# SOIC40_v1_r2.net
KiCad netlist of a schematic drawn in EAGLE
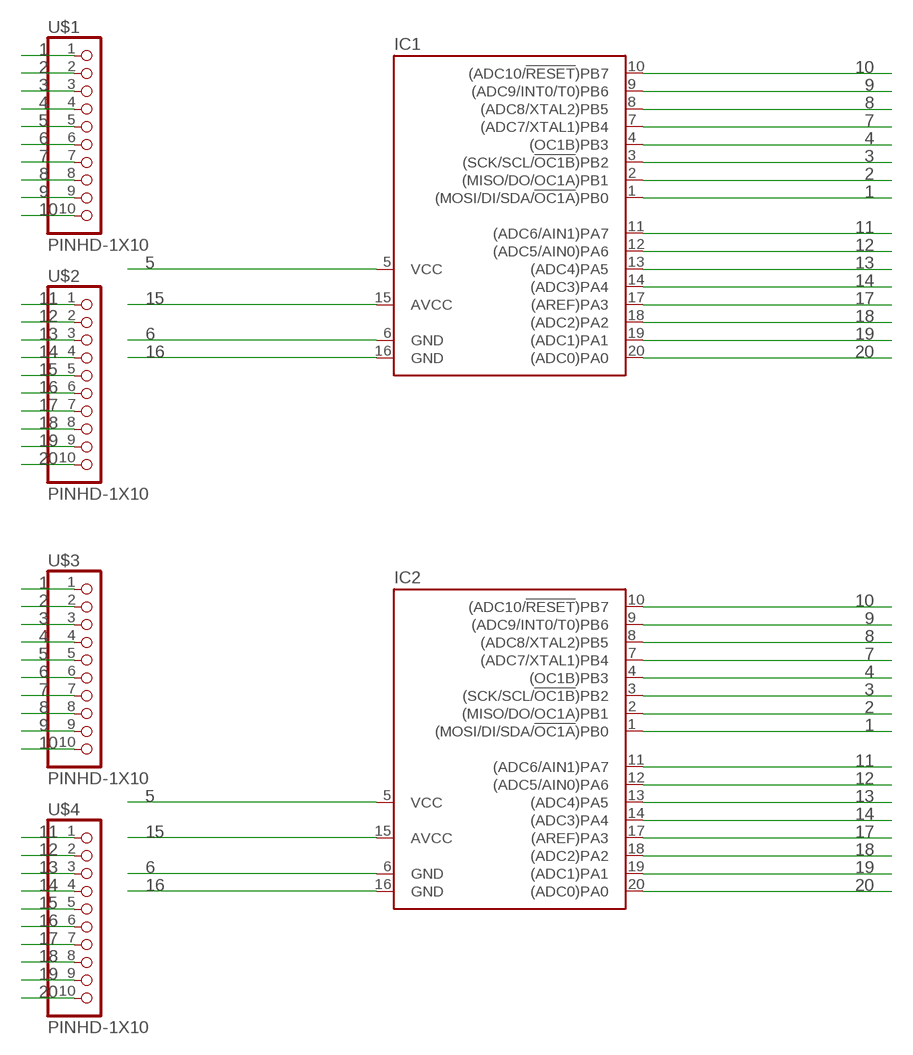
[diagram p0: schematic, sheet 1]

(export (version "E")
  (design (tool "Eeschema 10.0.6"))
  (components
    (comp (ref "IC1")
      (value "TINY26LS")
      (footprint "eagle-import:SO20L")
      (fields (field (name "MPN") "ATTINY26L-8SU"))
      (libsource (lib "eagle-import") (part "TINY26SL"))
    )
    (comp (ref "IC2")
      (value "TINY26LS")
      (footprint "eagle-import:SO20L")
      (fields (field (name "MPN") "ATTINY26L-8SU"))
      (libsource (lib "eagle-import") (part "TINY26SL"))
    )
    (comp (ref "U$1")
      (value "PINHD-1X10")
      (footprint "eagle-import:1X10-BIG")
      (libsource (lib "eagle-import") (part "PINHD-1X10"))
    )
    (comp (ref "U$2")
      (value "PINHD-1X10")
      (footprint "eagle-import:1X10-BIG")
      (libsource (lib "eagle-import") (part "PINHD-1X10"))
    )
    (comp (ref "U$3")
      (value "PINHD-1X10")
      (footprint "eagle-import:1X10-BIG")
      (libsource (lib "eagle-import") (part "PINHD-1X10"))
    )
    (comp (ref "U$4")
      (value "PINHD-1X10")
      (footprint "eagle-import:1X10-BIG")
      (libsource (lib "eagle-import") (part "PINHD-1X10"))
    )
  )
  (nets
    (net (code "1") (name "/1") (class "Default")
      (node (ref "IC1") (pin "1") (pinfunction "(MOSI/DI/SDA/~{OC1A})PB0_1") (pintype "bidirectional"))
      (node (ref "IC2") (pin "1") (pinfunction "(MOSI/DI/SDA/~{OC1A})PB0_1") (pintype "bidirectional"))
      (node (ref "U$1") (pin "1") (pinfunction "1_1") (pintype "passive"))
      (node (ref "U$3") (pin "1") (pinfunction "1_1") (pintype "passive"))
    )
    (net (code "2") (name "/2") (class "Default")
      (node (ref "IC1") (pin "2") (pinfunction "(MISO/DO/OC1A)PB1_2") (pintype "bidirectional"))
      (node (ref "IC2") (pin "2") (pinfunction "(MISO/DO/OC1A)PB1_2") (pintype "bidirectional"))
      (node (ref "U$1") (pin "2") (pinfunction "2_2") (pintype "passive"))
      (node (ref "U$3") (pin "2") (pinfunction "2_2") (pintype "passive"))
    )
    (net (code "3") (name "/3") (class "Default")
      (node (ref "IC1") (pin "3") (pinfunction "(SCK/SCL/~{OC1B})PB2_3") (pintype "bidirectional"))
      (node (ref "IC2") (pin "3") (pinfunction "(SCK/SCL/~{OC1B})PB2_3") (pintype "bidirectional"))
      (node (ref "U$1") (pin "3") (pinfunction "3_3") (pintype "passive"))
      (node (ref "U$3") (pin "3") (pinfunction "3_3") (pintype "passive"))
    )
    (net (code "4") (name "/4") (class "Default")
      (node (ref "IC1") (pin "4") (pinfunction "(OC1B)PB3_4") (pintype "bidirectional"))
      (node (ref "IC2") (pin "4") (pinfunction "(OC1B)PB3_4") (pintype "bidirectional"))
      (node (ref "U$1") (pin "4") (pinfunction "4_4") (pintype "passive"))
      (node (ref "U$3") (pin "4") (pinfunction "4_4") (pintype "passive"))
    )
    (net (code "5") (name "/5") (class "Default")
      (node (ref "IC1") (pin "5") (pinfunction "VCC_5") (pintype "power_in"))
      (node (ref "IC2") (pin "5") (pinfunction "VCC_5") (pintype "power_in"))
      (node (ref "U$1") (pin "5") (pinfunction "5_5") (pintype "passive"))
      (node (ref "U$3") (pin "5") (pinfunction "5_5") (pintype "passive"))
    )
    (net (code "6") (name "/6") (class "Default")
      (node (ref "IC1") (pin "6") (pinfunction "GND_6") (pintype "power_in"))
      (node (ref "IC2") (pin "6") (pinfunction "GND_6") (pintype "power_in"))
      (node (ref "U$1") (pin "6") (pinfunction "6_6") (pintype "passive"))
      (node (ref "U$3") (pin "6") (pinfunction "6_6") (pintype "passive"))
    )
    (net (code "7") (name "/7") (class "Default")
      (node (ref "IC1") (pin "7") (pinfunction "(ADC7/XTAL1)PB4_7") (pintype "bidirectional"))
      (node (ref "IC2") (pin "7") (pinfunction "(ADC7/XTAL1)PB4_7") (pintype "bidirectional"))
      (node (ref "U$1") (pin "7") (pinfunction "7_7") (pintype "passive"))
      (node (ref "U$3") (pin "7") (pinfunction "7_7") (pintype "passive"))
    )
    (net (code "8") (name "/8") (class "Default")
      (node (ref "IC1") (pin "8") (pinfunction "(ADC8/XTAL2)PB5_8") (pintype "bidirectional"))
      (node (ref "IC2") (pin "8") (pinfunction "(ADC8/XTAL2)PB5_8") (pintype "bidirectional"))
      (node (ref "U$1") (pin "8") (pinfunction "8_8") (pintype "passive"))
      (node (ref "U$3") (pin "8") (pinfunction "8_8") (pintype "passive"))
    )
    (net (code "9") (name "/9") (class "Default")
      (node (ref "IC1") (pin "9") (pinfunction "(ADC9/INT0/T0)PB6_9") (pintype "bidirectional"))
      (node (ref "IC2") (pin "9") (pinfunction "(ADC9/INT0/T0)PB6_9") (pintype "bidirectional"))
      (node (ref "U$1") (pin "9") (pinfunction "9_9") (pintype "passive"))
      (node (ref "U$3") (pin "9") (pinfunction "9_9") (pintype "passive"))
    )
    (net (code "10") (name "/10") (class "Default")
      (node (ref "IC1") (pin "10") (pinfunction "(ADC10/~{RESET})PB7_10") (pintype "bidirectional"))
      (node (ref "IC2") (pin "10") (pinfunction "(ADC10/~{RESET})PB7_10") (pintype "bidirectional"))
      (node (ref "U$1") (pin "10") (pinfunction "10_10") (pintype "passive"))
      (node (ref "U$3") (pin "10") (pinfunction "10_10") (pintype "passive"))
    )
    (net (code "11") (name "/11") (class "Default")
      (node (ref "IC1") (pin "11") (pinfunction "(ADC6/AIN1)PA7_11") (pintype "bidirectional"))
      (node (ref "IC2") (pin "11") (pinfunction "(ADC6/AIN1)PA7_11") (pintype "bidirectional"))
      (node (ref "U$2") (pin "1") (pinfunction "1_1") (pintype "passive"))
      (node (ref "U$4") (pin "1") (pinfunction "1_1") (pintype "passive"))
    )
    (net (code "12") (name "/12") (class "Default")
      (node (ref "IC1") (pin "12") (pinfunction "(ADC5/AIN0)PA6_12") (pintype "bidirectional"))
      (node (ref "IC2") (pin "12") (pinfunction "(ADC5/AIN0)PA6_12") (pintype "bidirectional"))
      (node (ref "U$2") (pin "2") (pinfunction "2_2") (pintype "passive"))
      (node (ref "U$4") (pin "2") (pinfunction "2_2") (pintype "passive"))
    )
    (net (code "13") (name "/13") (class "Default")
      (node (ref "IC1") (pin "13") (pinfunction "(ADC4)PA5_13") (pintype "bidirectional"))
      (node (ref "IC2") (pin "13") (pinfunction "(ADC4)PA5_13") (pintype "bidirectional"))
      (node (ref "U$2") (pin "3") (pinfunction "3_3") (pintype "passive"))
      (node (ref "U$4") (pin "3") (pinfunction "3_3") (pintype "passive"))
    )
    (net (code "14") (name "/14") (class "Default")
      (node (ref "IC1") (pin "14") (pinfunction "(ADC3)PA4_14") (pintype "bidirectional"))
      (node (ref "IC2") (pin "14") (pinfunction "(ADC3)PA4_14") (pintype "bidirectional"))
      (node (ref "U$2") (pin "4") (pinfunction "4_4") (pintype "passive"))
      (node (ref "U$4") (pin "4") (pinfunction "4_4") (pintype "passive"))
    )
    (net (code "15") (name "/15") (class "Default")
      (node (ref "IC1") (pin "15") (pinfunction "AVCC_15") (pintype "power_in"))
      (node (ref "IC2") (pin "15") (pinfunction "AVCC_15") (pintype "power_in"))
      (node (ref "U$2") (pin "5") (pinfunction "5_5") (pintype "passive"))
      (node (ref "U$4") (pin "5") (pinfunction "5_5") (pintype "passive"))
    )
    (net (code "16") (name "/16") (class "Default")
      (node (ref "IC1") (pin "16") (pinfunction "GND_16") (pintype "power_in"))
      (node (ref "IC2") (pin "16") (pinfunction "GND_16") (pintype "power_in"))
      (node (ref "U$2") (pin "6") (pinfunction "6_6") (pintype "passive"))
      (node (ref "U$4") (pin "6") (pinfunction "6_6") (pintype "passive"))
    )
    (net (code "17") (name "/17") (class "Default")
      (node (ref "IC1") (pin "17") (pinfunction "(AREF)PA3_17") (pintype "bidirectional"))
      (node (ref "IC2") (pin "17") (pinfunction "(AREF)PA3_17") (pintype "bidirectional"))
      (node (ref "U$2") (pin "7") (pinfunction "7_7") (pintype "passive"))
      (node (ref "U$4") (pin "7") (pinfunction "7_7") (pintype "passive"))
    )
    (net (code "18") (name "/18") (class "Default")
      (node (ref "IC1") (pin "18") (pinfunction "(ADC2)PA2_18") (pintype "bidirectional"))
      (node (ref "IC2") (pin "18") (pinfunction "(ADC2)PA2_18") (pintype "bidirectional"))
      (node (ref "U$2") (pin "8") (pinfunction "8_8") (pintype "passive"))
      (node (ref "U$4") (pin "8") (pinfunction "8_8") (pintype "passive"))
    )
    (net (code "19") (name "/19") (class "Default")
      (node (ref "IC1") (pin "19") (pinfunction "(ADC1)PA1_19") (pintype "bidirectional"))
      (node (ref "IC2") (pin "19") (pinfunction "(ADC1)PA1_19") (pintype "bidirectional"))
      (node (ref "U$2") (pin "9") (pinfunction "9_9") (pintype "passive"))
      (node (ref "U$4") (pin "9") (pinfunction "9_9") (pintype "passive"))
    )
    (net (code "20") (name "/20") (class "Default")
      (node (ref "IC1") (pin "20") (pinfunction "(ADC0)PA0_20") (pintype "bidirectional"))
      (node (ref "IC2") (pin "20") (pinfunction "(ADC0)PA0_20") (pintype "bidirectional"))
      (node (ref "U$2") (pin "10") (pinfunction "10_10") (pintype "passive"))
      (node (ref "U$4") (pin "10") (pinfunction "10_10") (pintype "passive"))
    )
  )
)
